# STM32F103ZET6_V2.net
KiCad netlist of a schematic drawn in Altium Designer
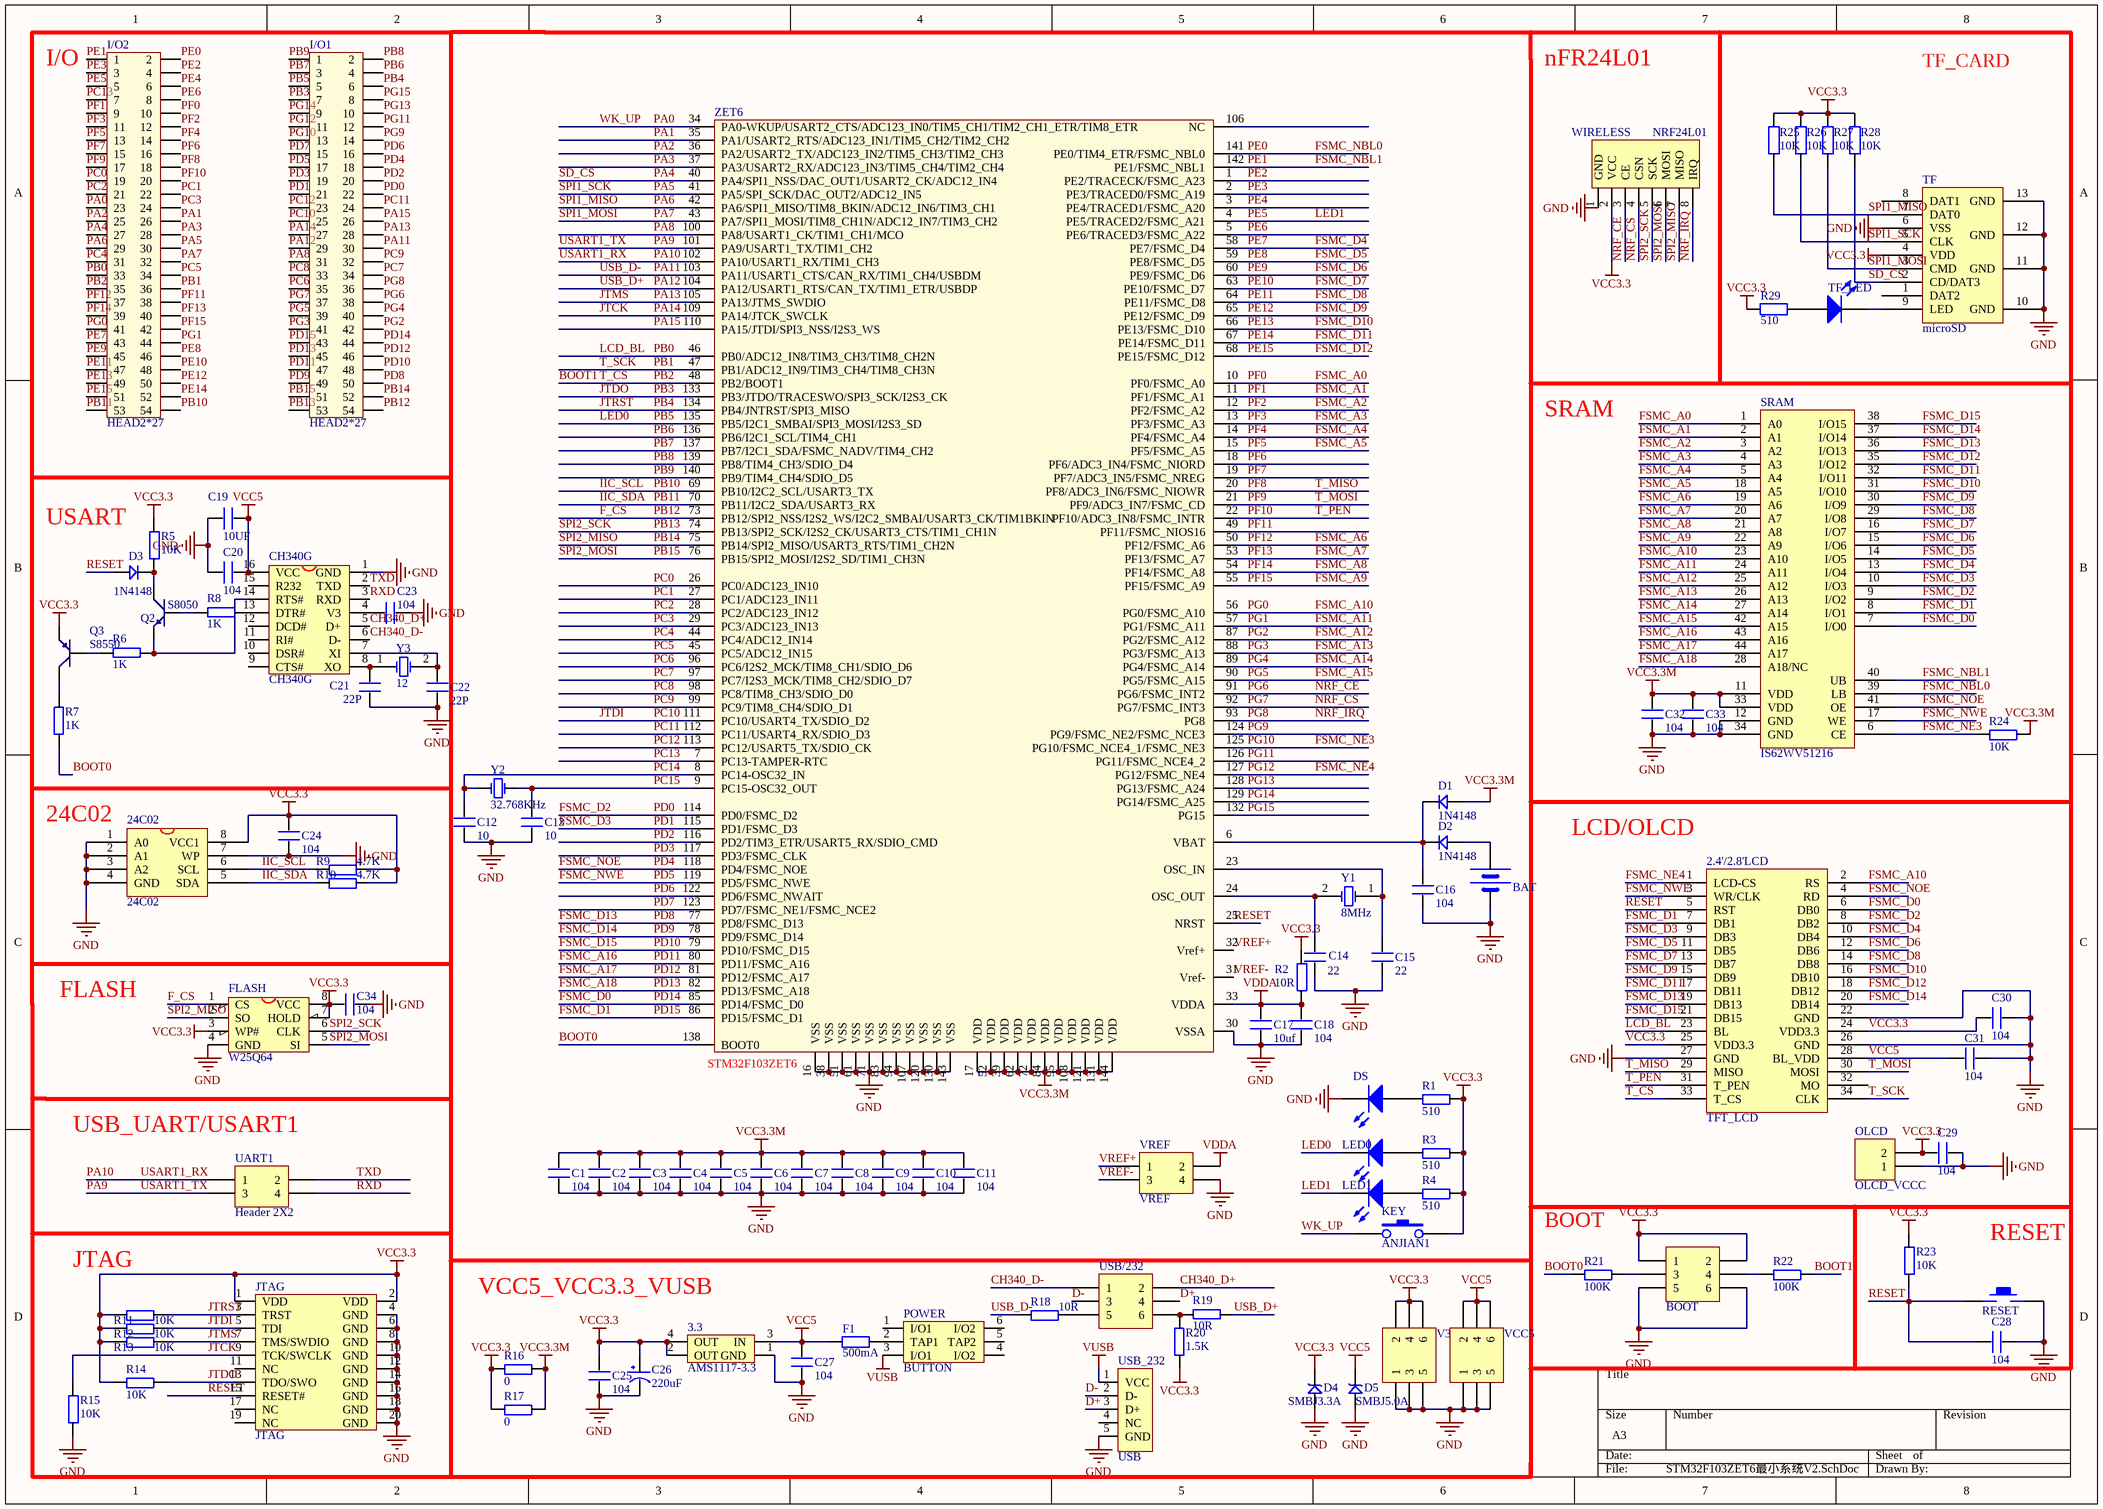
[diagram p0: STM32F103ZET6最小系统V2.SchDoc]

(export (version "E")
  (design (tool "Eeschema 10.0.6"))
  (components
    (comp (ref "2.4'/2.8'LCD")
      (value "TFT_LCD")
      (footprint "DB2*17")
      (libsource (lib "TFT_LCD") (part "TFT_LCD"))
    )
    (comp (ref "3.3")
      (value "AMS1117-3.3")
      (footprint "AMS1117")
      (libsource (lib "战舰STM32开发板底板封装库") (part "AMS1117"))
    )
    (comp (ref "24C02")
      (value "24C02")
      (footprint "SOP-8")
      (libsource (lib "战舰STM32开发板底板封装库") (part "24C256"))
    )
    (comp (ref "BAT") (value "BATT") (footprint "BATM") (libsource (lib "战舰STM32开发板底板封装库") (part "BAT")))
    (comp (ref "BOOT")
      (value "Header 3X2")
      (footprint "HDR2X3")
      (description "Header, 3-Pin, Dual row")
      (fields (field (name "PUBLISHER") "Altium Limited"))
      (libsource (lib "战舰STM32开发板底板封装库") (part "Header 3X2"))
    )
    (comp (ref "C1") (value "104") (footprint "0603P") (libsource (lib "战舰STM32开发板底板封装库") (part "C")))
    (comp (ref "C2") (value "104") (footprint "0603P") (libsource (lib "战舰STM32开发板底板封装库") (part "C")))
    (comp (ref "C3") (value "104") (footprint "0603P") (libsource (lib "战舰STM32开发板底板封装库") (part "C")))
    (comp (ref "C4") (value "104") (footprint "0603P") (libsource (lib "战舰STM32开发板底板封装库") (part "C")))
    (comp (ref "C5") (value "104") (footprint "0603P") (libsource (lib "战舰STM32开发板底板封装库") (part "C")))
    (comp (ref "C6") (value "104") (footprint "0603P") (libsource (lib "战舰STM32开发板底板封装库") (part "C")))
    (comp (ref "C7") (value "104") (footprint "0603P") (libsource (lib "战舰STM32开发板底板封装库") (part "C")))
    (comp (ref "C8") (value "104") (footprint "0603P") (libsource (lib "战舰STM32开发板底板封装库") (part "C")))
    (comp (ref "C9") (value "104") (footprint "0603P") (libsource (lib "战舰STM32开发板底板封装库") (part "C")))
    (comp (ref "C10") (value "104") (footprint "0603P") (libsource (lib "战舰STM32开发板底板封装库") (part "C")))
    (comp (ref "C11") (value "104") (footprint "0603P") (libsource (lib "战舰STM32开发板底板封装库") (part "C")))
    (comp (ref "C12") (value "10") (footprint "0603P") (libsource (lib "战舰STM32开发板底板封装库") (part "C_2")))
    (comp (ref "C13") (value "10") (footprint "0603P") (libsource (lib "战舰STM32开发板底板封装库") (part "C_2")))
    (comp (ref "C14") (value "22") (footprint "0805") (libsource (lib "战舰STM32开发板底板封装库") (part "C_1")))
    (comp (ref "C15") (value "22") (footprint "0805") (libsource (lib "战舰STM32开发板底板封装库") (part "C_1")))
    (comp (ref "C16") (value "104") (footprint "0805") (libsource (lib "战舰STM32开发板底板封装库") (part "C_1")))
    (comp (ref "C17") (value "10uf") (footprint "0805") (libsource (lib "战舰STM32开发板底板封装库") (part "C_1")))
    (comp (ref "C18") (value "104") (footprint "0603P") (libsource (lib "战舰STM32开发板底板封装库") (part "C_1")))
    (comp (ref "C19") (value "10UF") (footprint "0805") (libsource (lib "战舰STM32开发板底板封装库") (part "C_1")))
    (comp (ref "C20") (value "104") (footprint "0805") (libsource (lib "战舰STM32开发板底板封装库") (part "C_1")))
    (comp (ref "C21") (value "22P") (footprint "0805") (libsource (lib "战舰STM32开发板底板封装库") (part "C_2")))
    (comp (ref "C22") (value "22P") (footprint "0805") (libsource (lib "战舰STM32开发板底板封装库") (part "C_2")))
    (comp (ref "C23") (value "104") (footprint "0805") (libsource (lib "战舰STM32开发板底板封装库") (part "C_1")))
    (comp (ref "C24") (value "104") (footprint "0805") (libsource (lib "战舰STM32开发板底板封装库") (part "C_1")))
    (comp (ref "C25") (value "104") (footprint "0805") (libsource (lib "战舰STM32开发板底板封装库") (part "C_1")))
    (comp (ref "C26") (value "220uF") (footprint "CC6.56.5") (libsource (lib "战舰STM32开发板底板封装库") (part "CAP")))
    (comp (ref "C27") (value "104") (footprint "0805") (libsource (lib "战舰STM32开发板底板封装库") (part "C")))
    (comp (ref "C28") (value "104") (footprint "0805") (libsource (lib "战舰STM32开发板底板封装库") (part "C")))
    (comp (ref "C29") (value "104") (footprint "0805") (libsource (lib "战舰STM32开发板底板封装库") (part "C_1")))
    (comp (ref "C30") (value "104") (footprint "0805") (libsource (lib "战舰STM32开发板底板封装库") (part "C")))
    (comp (ref "C31") (value "104") (footprint "0805") (libsource (lib "战舰STM32开发板底板封装库") (part "C")))
    (comp (ref "C32") (value "104") (footprint "0805") (libsource (lib "战舰STM32开发板底板封装库") (part "C_1")))
    (comp (ref "C33") (value "104") (footprint "0805") (libsource (lib "战舰STM32开发板底板封装库") (part "C_1")))
    (comp (ref "C34") (value "104") (footprint "0805") (libsource (lib "战舰STM32开发板底板封装库") (part "C_1")))
    (comp (ref "CH340G")
      (value "CH340G")
      (footprint "SOP16M")
      (description "USB2UART")
      (libsource (lib "战舰STM32开发板底板封装库") (part "CH340G"))
    )
    (comp (ref "D1") (value "1N4148") (footprint "DIODE_SOP") (libsource (lib "战舰STM32开发板底板封装库") (part "D")))
    (comp (ref "D2") (value "1N4148") (footprint "DIODE_SOP") (libsource (lib "战舰STM32开发板底板封装库") (part "D")))
    (comp (ref "D3") (value "1N4148") (footprint "DIODE_SOP") (libsource (lib "战舰STM32开发板底板封装库") (part "D")))
    (comp (ref "D4")
      (value "SMBJ5.0A")
      (footprint "SMBJ")
      (description "TVS")
      (libsource (lib "战舰STM32开发板底板封装库") (part "SMBJ"))
    )
    (comp (ref "D5")
      (value "SMBJ3.3A")
      (footprint "SMBJ")
      (description "TVS")
      (libsource (lib "战舰STM32开发板底板封装库") (part "SMBJ"))
    )
    (comp (ref "DS")
      (value "LED1")
      (footprint "0805")
      (description "Typical RED, GREEN, YELLOW, AMBER GaAs LED")
      (fields (field (name "PUBLISHER") "Altium Limited"))
      (libsource (lib "战舰STM32开发板底板封装库") (part "LED2"))
    )
    (comp (ref "F1")
      (value "500mA")
      (footprint "0805")
      (description "Resistor")
      (fields (field (name "Comment") "Res2") (field (name "PUBLISHER") "Altium Limited"))
      (libsource (lib "") (part "Res2_2"))
    )
    (comp (ref "FLASH")
      (value "W25Q64")
      (footprint "SOIC-8")
      (description "W25X16;SST25VF016;MX25L1605")
      (libsource (lib "战舰STM32开发板底板封装库") (part "W25X16"))
    )
    (comp (ref "I/O1")
      (value "HEAD2*27")
      (footprint "HEAD2*27")
      (libsource (lib "战舰STM32开发板底板封装库") (part "HEAD2*27"))
    )
    (comp (ref "I/O2")
      (value "HEAD2*27")
      (footprint "HEAD2*27")
      (libsource (lib "战舰STM32开发板底板封装库") (part "HEAD2*27"))
    )
    (comp (ref "JTAG") (value "JTAG") (footprint "HDR2X10") (libsource (lib "战舰STM32开发板底板封装库") (part "JTAG")))
    (comp (ref "KEY") (value "ANJIAN1") (footprint "贴片微动开关") (libsource (lib "开关") (part "ANJIAN1")))
    (comp (ref "LED0")
      (value "LED1")
      (footprint "0805")
      (description "Typical RED, GREEN, YELLOW, AMBER GaAs LED")
      (fields (field (name "PUBLISHER") "Altium Limited"))
      (libsource (lib "战舰STM32开发板底板封装库") (part "LED2"))
    )
    (comp (ref "LED1")
      (value "LED1")
      (footprint "0805")
      (description "Typical RED, GREEN, YELLOW, AMBER GaAs LED")
      (fields (field (name "PUBLISHER") "Altium Limited"))
      (libsource (lib "战舰STM32开发板底板封装库") (part "LED2"))
    )
    (comp (ref "OLCD")
      (value "OLCD_VCCC")
      (footprint "HDR1X2")
      (description "Header, 2-Pin, Right Angle")
      (fields (field (name "PUBLISHER") "Altium Limited"))
      (libsource (lib "Miscellaneous Connectors") (part "Header 2H"))
    )
    (comp (ref "POWER")
      (value "BUTTON")
      (footprint "BTN8.5*8.5")
      (libsource (lib "战舰STM32开发板底板封装库") (part "BUTTON"))
    )
    (comp (ref "Q2")
      (value "S8050")
      (footprint "SOT-23R")
      (description "8050/BCW846/BCW847")
      (libsource (lib "战舰STM32开发板底板封装库") (part "NPN"))
    )
    (comp (ref "Q3")
      (value "S8550")
      (footprint "SOT-23R")
      (description "8550/BCW68")
      (libsource (lib "战舰STM32开发板底板封装库") (part "PNP"))
    )
    (comp (ref "R1") (value "510") (footprint "0805") (libsource (lib "战舰STM32开发板底板封装库") (part "R")))
    (comp (ref "R2") (value "10R") (footprint "0805") (libsource (lib "战舰STM32开发板底板封装库") (part "R")))
    (comp (ref "R3") (value "510") (footprint "0805") (libsource (lib "战舰STM32开发板底板封装库") (part "R")))
    (comp (ref "R4") (value "510") (footprint "0805") (libsource (lib "战舰STM32开发板底板封装库") (part "R")))
    (comp (ref "R5") (value "10K") (footprint "0805") (libsource (lib "战舰STM32开发板底板封装库") (part "R")))
    (comp (ref "R6") (value "1K") (footprint "0805") (libsource (lib "战舰STM32开发板底板封装库") (part "R")))
    (comp (ref "R7") (value "1K") (footprint "0805") (libsource (lib "战舰STM32开发板底板封装库") (part "R")))
    (comp (ref "R8") (value "1K") (footprint "0805") (libsource (lib "战舰STM32开发板底板封装库") (part "R")))
    (comp (ref "R9") (value "4.7K") (footprint "0805") (libsource (lib "战舰STM32开发板底板封装库") (part "R")))
    (comp (ref "R10") (value "4.7K") (footprint "0805") (libsource (lib "战舰STM32开发板底板封装库") (part "R")))
    (comp (ref "R11") (value "10K") (footprint "0805") (libsource (lib "战舰STM32开发板底板封装库") (part "R_1")))
    (comp (ref "R12") (value "10K") (footprint "0805") (libsource (lib "战舰STM32开发板底板封装库") (part "R_1")))
    (comp (ref "R13") (value "10K") (footprint "0805") (libsource (lib "战舰STM32开发板底板封装库") (part "R_1")))
    (comp (ref "R14") (value "10K") (footprint "0805") (libsource (lib "战舰STM32开发板底板封装库") (part "R_1")))
    (comp (ref "R15") (value "10K") (footprint "0805") (libsource (lib "战舰STM32开发板底板封装库") (part "R_1")))
    (comp (ref "R16") (value "0") (footprint "0805") (libsource (lib "战舰STM32开发板底板封装库") (part "R")))
    (comp (ref "R17") (value "0") (footprint "0805") (libsource (lib "战舰STM32开发板底板封装库") (part "R")))
    (comp (ref "R18") (value "10R") (footprint "0805") (libsource (lib "战舰STM32开发板底板封装库") (part "R_2")))
    (comp (ref "R19") (value "10R") (footprint "0805") (libsource (lib "战舰STM32开发板底板封装库") (part "R_2")))
    (comp (ref "R20") (value "1.5K") (footprint "0805") (libsource (lib "战舰STM32开发板底板封装库") (part "R_2")))
    (comp (ref "R21") (value "100K") (footprint "0805") (libsource (lib "战舰STM32开发板底板封装库") (part "R_1")))
    (comp (ref "R22") (value "100K") (footprint "0805") (libsource (lib "战舰STM32开发板底板封装库") (part "R_1")))
    (comp (ref "R23") (value "10K") (footprint "0805") (libsource (lib "战舰STM32开发板底板封装库") (part "R_1")))
    (comp (ref "R24") (value "10K") (footprint "0805") (libsource (lib "战舰STM32开发板底板封装库") (part "R")))
    (comp (ref "R25")
      (value "10K")
      (footprint "0805")
      (description "Resistor")
      (fields (field (name "Comment") "Res2") (field (name "PUBLISHER") "Altium Limited"))
      (libsource (lib "Miscellaneous Devices") (part "Res2"))
    )
    (comp (ref "R26")
      (value "10K")
      (footprint "0805")
      (description "Resistor")
      (fields (field (name "Comment") "Res2") (field (name "PUBLISHER") "Altium Limited"))
      (libsource (lib "Miscellaneous Devices") (part "Res2"))
    )
    (comp (ref "R27")
      (value "10K")
      (footprint "0805")
      (description "Resistor")
      (fields (field (name "Comment") "Res2") (field (name "PUBLISHER") "Altium Limited"))
      (libsource (lib "Miscellaneous Devices") (part "Res2"))
    )
    (comp (ref "R28")
      (value "10K")
      (footprint "0805")
      (description "Resistor")
      (fields (field (name "Comment") "Res2") (field (name "PUBLISHER") "Altium Limited"))
      (libsource (lib "Miscellaneous Devices") (part "Res2"))
    )
    (comp (ref "R29")
      (value "510")
      (footprint "0805")
      (description "Resistor")
      (fields (field (name "Comment") "Res2") (field (name "PUBLISHER") "Altium Limited"))
      (libsource (lib "") (part "Res2_1"))
    )
    (comp (ref "RESET")
      (value "KEY_M")
      (footprint "贴片微动开关")
      (libsource (lib "战舰STM32开发板底板封装库") (part "KEY_M"))
    )
    (comp (ref "SRAM")
      (value "IS62WV51216")
      (footprint "TSOP44")
      (libsource (lib "STM32F103常用外设") (part "SRAM"))
    )
    (comp (ref "TF") (value "microSD") (footprint "TF_CARD") (libsource (lib "我自己的库") (part "microSD")))
    (comp (ref "TF_LED")
      (value "LED1")
      (footprint "0805")
      (description "Typical RED, GREEN, YELLOW, AMBER GaAs LED")
      (fields (field (name "PUBLISHER") "Altium Limited"))
      (libsource (lib "战舰STM32开发板底板封装库") (part "LED2"))
    )
    (comp (ref "UART1")
      (value "Header 2X2")
      (footprint "HDR2X2")
      (description "Header, 2-Pin, Dual row")
      (fields (field (name "PUBLISHER") "Altium Limited"))
      (libsource (lib "Miscellaneous Connectors") (part "Header 2X2"))
    )
    (comp (ref "USB/232")
      (value "Header 3X2")
      (footprint "HDR2X3")
      (description "Header, 3-Pin, Dual row")
      (fields (field (name "PUBLISHER") "Altium Limited"))
      (libsource (lib "战舰STM32开发板底板封装库") (part "Header 3X2"))
    )
    (comp (ref "USB_232")
      (value "USB")
      (footprint "USB/SM0.8-6H5")
      (libsource (lib "战舰STM32开发板底板封装库") (part "USB5"))
    )
    (comp (ref "V3.3")
      (value "Header 3X2")
      (footprint "HDR2X3")
      (description "Header, 3-Pin, Dual row")
      (fields (field (name "PUBLISHER") "Altium Limited"))
      (libsource (lib "Miscellaneous Connectors") (part "Header 3X2"))
    )
    (comp (ref "VCC5")
      (value "Header 3X2")
      (footprint "HDR2X3")
      (description "Header, 3-Pin, Dual row")
      (fields (field (name "PUBLISHER") "Altium Limited"))
      (libsource (lib "Miscellaneous Connectors") (part "Header 3X2"))
    )
    (comp (ref "VREF")
      (value "VREF")
      (footprint "HDR2X2")
      (description "Header, 2-Pin, Dual row")
      (fields (field (name "PUBLISHER") "Altium Limited"))
      (libsource (lib "战舰STM32开发板底板封装库") (part "Header 2X2"))
    )
    (comp (ref "WIRELESS")
      (value "NRF24L01")
      (footprint "NRF24L01")
      (libsource (lib "战舰STM32开发板底板封装库") (part "NRF24L01"))
    )
    (comp (ref "Y1")
      (value "8MHz")
      (footprint "XTAL_US")
      (description "Crystal Oscillator")
      (fields (field (name "PUBLISHER") "Altium Limited"))
      (libsource (lib "战舰STM32开发板底板封装库") (part "XTAL"))
    )
    (comp (ref "Y2")
      (value "32.768KHz")
      (footprint "XTAL32")
      (description "32.768K")
      (fields (field (name "PUBLISHER") "Altium Limited"))
      (libsource (lib "战舰STM32开发板底板封装库") (part "XTAL_3"))
    )
    (comp (ref "Y3")
      (value "12")
      (footprint "XTAL_US")
      (description "Crystal Oscillator")
      (fields (field (name "PUBLISHER") "Altium Limited"))
      (libsource (lib "战舰STM32开发板底板封装库") (part "XTAL"))
    )
    (comp (ref "ZET6")
      (value "STM32F103ZET6")
      (footprint "LQFP144")
      (libsource (lib "stm32") (part "STM32F103ZET6"))
    )
  )
  (nets
    (net (code "1") (name "/BOOT0") (class "Default")
      (node (ref "R21") (pin "1") (pintype "passive"))
      (node (ref "R7") (pin "2") (pintype "passive"))
      (node (ref "ZET6") (pin "138") (pinfunction "BOOT0_138") (pintype "passive"))
    )
    (net (code "2") (name "/BOOT1") (class "Default")
      (node (ref "2.4'/2.8'LCD") (pin "33") (pinfunction "T_CS_33") (pintype "passive"))
      (node (ref "I/O2") (pin "35") (pinfunction "35_35") (pintype "passive"))
      (node (ref "R22") (pin "2") (pintype "passive"))
      (node (ref "ZET6") (pin "48") (pinfunction "PB2/BOOT1_48") (pintype "passive"))
    )
    (net (code "3") (name "/CH340_D+") (class "Default")
      (node (ref "CH340G") (pin "5") (pinfunction "D+_5") (pintype "passive"))
      (node (ref "USB/232") (pin "2") (pinfunction "2_2") (pintype "passive"))
    )
    (net (code "4") (name "/CH340_D-") (class "Default")
      (node (ref "CH340G") (pin "6") (pinfunction "D-_6") (pintype "passive"))
      (node (ref "USB/232") (pin "1") (pinfunction "1_1") (pintype "passive"))
    )
    (net (code "5") (name "/D+") (class "Default")
      (node (ref "USB/232") (pin "4") (pinfunction "4_4") (pintype "passive"))
      (node (ref "USB_232") (pin "3") (pinfunction "D+_3") (pintype "passive"))
    )
    (net (code "6") (name "/D-") (class "Default")
      (node (ref "USB/232") (pin "3") (pinfunction "3_3") (pintype "passive"))
      (node (ref "USB_232") (pin "2") (pinfunction "D-_2") (pintype "passive"))
    )
    (net (code "7") (name "/FSMC_A0") (class "Default")
      (node (ref "I/O2") (pin "10") (pinfunction "10_10") (pintype "passive"))
      (node (ref "SRAM") (pin "1") (pinfunction "A0_1") (pintype "passive"))
      (node (ref "ZET6") (pin "10") (pinfunction "PF0/FSMC_A0_10") (pintype "passive"))
    )
    (net (code "8") (name "/FSMC_A1") (class "Default")
      (node (ref "I/O2") (pin "9") (pinfunction "9_9") (pintype "passive"))
      (node (ref "SRAM") (pin "2") (pinfunction "A1_2") (pintype "passive"))
      (node (ref "ZET6") (pin "11") (pinfunction "PF1/FSMC_A1_11") (pintype "passive"))
    )
    (net (code "9") (name "/FSMC_A2") (class "Default")
      (node (ref "I/O2") (pin "12") (pinfunction "12_12") (pintype "passive"))
      (node (ref "SRAM") (pin "3") (pinfunction "A2_3") (pintype "passive"))
      (node (ref "ZET6") (pin "12") (pinfunction "PF2/FSMC_A2_12") (pintype "passive"))
    )
    (net (code "10") (name "/FSMC_A3") (class "Default")
      (node (ref "I/O2") (pin "11") (pinfunction "11_11") (pintype "passive"))
      (node (ref "SRAM") (pin "4") (pinfunction "A3_4") (pintype "passive"))
      (node (ref "ZET6") (pin "13") (pinfunction "PF3/FSMC_A3_13") (pintype "passive"))
    )
    (net (code "11") (name "/FSMC_A4") (class "Default")
      (node (ref "I/O2") (pin "14") (pinfunction "14_14") (pintype "passive"))
      (node (ref "SRAM") (pin "5") (pinfunction "A4_5") (pintype "passive"))
      (node (ref "ZET6") (pin "14") (pinfunction "PF4/FSMC_A4_14") (pintype "passive"))
    )
    (net (code "12") (name "/FSMC_A5") (class "Default")
      (node (ref "I/O2") (pin "13") (pinfunction "13_13") (pintype "passive"))
      (node (ref "SRAM") (pin "18") (pinfunction "A5_18") (pintype "passive"))
      (node (ref "ZET6") (pin "15") (pinfunction "PF5/FSMC_A5_15") (pintype "passive"))
    )
    (net (code "13") (name "/FSMC_A6") (class "Default")
      (node (ref "I/O2") (pin "37") (pinfunction "37_37") (pintype "passive"))
      (node (ref "SRAM") (pin "19") (pinfunction "A6_19") (pintype "passive"))
      (node (ref "ZET6") (pin "50") (pinfunction "PF12/FSMC_A6_50") (pintype "passive"))
    )
    (net (code "14") (name "/FSMC_A7") (class "Default")
      (node (ref "I/O2") (pin "40") (pinfunction "40_40") (pintype "passive"))
      (node (ref "SRAM") (pin "20") (pinfunction "A7_20") (pintype "passive"))
      (node (ref "ZET6") (pin "53") (pinfunction "PF13/FSMC_A7_53") (pintype "passive"))
    )
    (net (code "15") (name "/FSMC_A8") (class "Default")
      (node (ref "I/O2") (pin "39") (pinfunction "39_39") (pintype "passive"))
      (node (ref "SRAM") (pin "21") (pinfunction "A8_21") (pintype "passive"))
      (node (ref "ZET6") (pin "54") (pinfunction "PF14/FSMC_A8_54") (pintype "passive"))
    )
    (net (code "16") (name "/FSMC_A9") (class "Default")
      (node (ref "I/O2") (pin "42") (pinfunction "42_42") (pintype "passive"))
      (node (ref "SRAM") (pin "22") (pinfunction "A9_22") (pintype "passive"))
      (node (ref "ZET6") (pin "55") (pinfunction "PF15/FSMC_A9_55") (pintype "passive"))
    )
    (net (code "17") (name "/FSMC_A10") (class "Default")
      (node (ref "2.4'/2.8'LCD") (pin "2") (pinfunction "RS_2") (pintype "passive"))
      (node (ref "I/O2") (pin "41") (pinfunction "41_41") (pintype "passive"))
      (node (ref "SRAM") (pin "23") (pinfunction "A10_23") (pintype "passive"))
      (node (ref "ZET6") (pin "56") (pinfunction "PG0/FSMC_A10_56") (pintype "passive"))
    )
    (net (code "18") (name "/FSMC_A11") (class "Default")
      (node (ref "I/O2") (pin "44") (pinfunction "44_44") (pintype "passive"))
      (node (ref "SRAM") (pin "24") (pinfunction "A11_24") (pintype "passive"))
      (node (ref "ZET6") (pin "57") (pinfunction "PG1/FSMC_A11_57") (pintype "passive"))
    )
    (net (code "19") (name "/FSMC_A12") (class "Default")
      (node (ref "I/O1") (pin "42") (pinfunction "42_42") (pintype "passive"))
      (node (ref "SRAM") (pin "25") (pinfunction "A12_25") (pintype "passive"))
      (node (ref "ZET6") (pin "87") (pinfunction "PG2/FSMC_A12_87") (pintype "passive"))
    )
    (net (code "20") (name "/FSMC_A13") (class "Default")
      (node (ref "I/O1") (pin "41") (pinfunction "41_41") (pintype "passive"))
      (node (ref "SRAM") (pin "26") (pinfunction "A13_26") (pintype "passive"))
      (node (ref "ZET6") (pin "88") (pinfunction "PG3/FSMC_A13_88") (pintype "passive"))
    )
    (net (code "21") (name "/FSMC_A14") (class "Default")
      (node (ref "I/O1") (pin "40") (pinfunction "40_40") (pintype "passive"))
      (node (ref "SRAM") (pin "27") (pinfunction "A14_27") (pintype "passive"))
      (node (ref "ZET6") (pin "89") (pinfunction "PG4/FSMC_A14_89") (pintype "passive"))
    )
    (net (code "22") (name "/FSMC_A15") (class "Default")
      (node (ref "I/O1") (pin "39") (pinfunction "39_39") (pintype "passive"))
      (node (ref "SRAM") (pin "42") (pinfunction "A15_42") (pintype "passive"))
      (node (ref "ZET6") (pin "90") (pinfunction "PG5/FSMC_A15_90") (pintype "passive"))
    )
    (net (code "23") (name "/FSMC_A16") (class "Default")
      (node (ref "I/O1") (pin "47") (pinfunction "47_47") (pintype "passive"))
      (node (ref "SRAM") (pin "43") (pinfunction "A16_43") (pintype "passive"))
      (node (ref "ZET6") (pin "80") (pinfunction "PD11/FSMC_A16_80") (pintype "passive"))
    )
    (net (code "24") (name "/FSMC_A17") (class "Default")
      (node (ref "I/O1") (pin "46") (pinfunction "46_46") (pintype "passive"))
      (node (ref "SRAM") (pin "44") (pinfunction "A17_44") (pintype "passive"))
      (node (ref "ZET6") (pin "81") (pinfunction "PD12/FSMC_A17_81") (pintype "passive"))
    )
    (net (code "25") (name "/FSMC_A18") (class "Default")
      (node (ref "I/O1") (pin "45") (pinfunction "45_45") (pintype "passive"))
      (node (ref "SRAM") (pin "28") (pinfunction "A18/NC_28") (pintype "passive"))
      (node (ref "ZET6") (pin "82") (pinfunction "PD13/FSMC_A18_82") (pintype "passive"))
    )
    (net (code "26") (name "/FSMC_D0") (class "Default")
      (node (ref "2.4'/2.8'LCD") (pin "6") (pinfunction "DB0_6") (pintype "passive"))
      (node (ref "I/O1") (pin "44") (pinfunction "44_44") (pintype "passive"))
      (node (ref "SRAM") (pin "7") (pinfunction "I/O0_7") (pintype "passive"))
      (node (ref "ZET6") (pin "85") (pinfunction "PD14/FSMC_D0_85") (pintype "passive"))
    )
    (net (code "27") (name "/FSMC_D1") (class "Default")
      (node (ref "2.4'/2.8'LCD") (pin "7") (pinfunction "DB1_7") (pintype "passive"))
      (node (ref "I/O1") (pin "43") (pinfunction "43_43") (pintype "passive"))
      (node (ref "SRAM") (pin "8") (pinfunction "I/O1_8") (pintype "passive"))
      (node (ref "ZET6") (pin "86") (pinfunction "PD15/FSMC_D1_86") (pintype "passive"))
    )
    (net (code "28") (name "/FSMC_D2") (class "Default")
      (node (ref "2.4'/2.8'LCD") (pin "8") (pinfunction "DB2_8") (pintype "passive"))
      (node (ref "I/O1") (pin "22") (pinfunction "22_22") (pintype "passive"))
      (node (ref "SRAM") (pin "9") (pinfunction "I/O2_9") (pintype "passive"))
      (node (ref "ZET6") (pin "114") (pinfunction "PD0/FSMC_D2_114") (pintype "passive"))
    )
    (net (code "29") (name "/FSMC_D3") (class "Default")
      (node (ref "2.4'/2.8'LCD") (pin "9") (pinfunction "DB3_9") (pintype "passive"))
      (node (ref "I/O1") (pin "21") (pinfunction "21_21") (pintype "passive"))
      (node (ref "SRAM") (pin "10") (pinfunction "I/O3_10") (pintype "passive"))
      (node (ref "ZET6") (pin "115") (pinfunction "PD1/FSMC_D3_115") (pintype "passive"))
    )
    (net (code "30") (name "/FSMC_D4") (class "Default")
      (node (ref "2.4'/2.8'LCD") (pin "10") (pinfunction "DB4_10") (pintype "passive"))
      (node (ref "I/O2") (pin "43") (pinfunction "43_43") (pintype "passive"))
      (node (ref "SRAM") (pin "13") (pinfunction "I/O4_13") (pintype "passive"))
      (node (ref "ZET6") (pin "58") (pinfunction "PE7/FSMC_D4_58") (pintype "passive"))
    )
    (net (code "31") (name "/FSMC_D5") (class "Default")
      (node (ref "2.4'/2.8'LCD") (pin "11") (pinfunction "DB5_11") (pintype "passive"))
      (node (ref "I/O2") (pin "46") (pinfunction "46_46") (pintype "passive"))
      (node (ref "SRAM") (pin "14") (pinfunction "I/O5_14") (pintype "passive"))
      (node (ref "ZET6") (pin "59") (pinfunction "PE8/FSMC_D5_59") (pintype "passive"))
    )
    (net (code "32") (name "/FSMC_D6") (class "Default")
      (node (ref "2.4'/2.8'LCD") (pin "12") (pinfunction "DB6_12") (pintype "passive"))
      (node (ref "I/O2") (pin "45") (pinfunction "45_45") (pintype "passive"))
      (node (ref "SRAM") (pin "15") (pinfunction "I/O6_15") (pintype "passive"))
      (node (ref "ZET6") (pin "60") (pinfunction "PE9/FSMC_D6_60") (pintype "passive"))
    )
    (net (code "33") (name "/FSMC_D7") (class "Default")
      (node (ref "2.4'/2.8'LCD") (pin "13") (pinfunction "DB7_13") (pintype "passive"))
      (node (ref "I/O2") (pin "48") (pinfunction "48_48") (pintype "passive"))
      (node (ref "SRAM") (pin "16") (pinfunction "I/O7_16") (pintype "passive"))
      (node (ref "ZET6") (pin "63") (pinfunction "PE10/FSMC_D7_63") (pintype "passive"))
    )
    (net (code "34") (name "/FSMC_D8") (class "Default")
      (node (ref "2.4'/2.8'LCD") (pin "14") (pinfunction "DB8_14") (pintype "passive"))
      (node (ref "I/O2") (pin "47") (pinfunction "47_47") (pintype "passive"))
      (node (ref "SRAM") (pin "29") (pinfunction "I/O8_29") (pintype "passive"))
      (node (ref "ZET6") (pin "64") (pinfunction "PE11/FSMC_D8_64") (pintype "passive"))
    )
    (net (code "35") (name "/FSMC_D9") (class "Default")
      (node (ref "2.4'/2.8'LCD") (pin "15") (pinfunction "DB9_15") (pintype "passive"))
      (node (ref "I/O2") (pin "50") (pinfunction "50_50") (pintype "passive"))
      (node (ref "SRAM") (pin "30") (pinfunction "I/O9_30") (pintype "passive"))
      (node (ref "ZET6") (pin "65") (pinfunction "PE12/FSMC_D9_65") (pintype "passive"))
    )
    (net (code "36") (name "/FSMC_D10") (class "Default")
      (node (ref "2.4'/2.8'LCD") (pin "16") (pinfunction "DB10_16") (pintype "passive"))
      (node (ref "I/O2") (pin "49") (pinfunction "49_49") (pintype "passive"))
      (node (ref "SRAM") (pin "31") (pinfunction "I/O10_31") (pintype "passive"))
      (node (ref "ZET6") (pin "66") (pinfunction "PE13/FSMC_D10_66") (pintype "passive"))
    )
    (net (code "37") (name "/FSMC_D11") (class "Default")
      (node (ref "2.4'/2.8'LCD") (pin "17") (pinfunction "DB11_17") (pintype "passive"))
      (node (ref "I/O2") (pin "52") (pinfunction "52_52") (pintype "passive"))
      (node (ref "SRAM") (pin "32") (pinfunction "I/O11_32") (pintype "passive"))
      (node (ref "ZET6") (pin "67") (pinfunction "PE14/FSMC_D11_67") (pintype "passive"))
    )
    (net (code "38") (name "/FSMC_D12") (class "Default")
      (node (ref "2.4'/2.8'LCD") (pin "18") (pinfunction "DB12_18") (pintype "passive"))
      (node (ref "I/O2") (pin "51") (pinfunction "51_51") (pintype "passive"))
      (node (ref "SRAM") (pin "35") (pinfunction "I/O12_35") (pintype "passive"))
      (node (ref "ZET6") (pin "68") (pinfunction "PE15/FSMC_D12_68") (pintype "passive"))
    )
    (net (code "39") (name "/FSMC_D13") (class "Default")
      (node (ref "2.4'/2.8'LCD") (pin "19") (pinfunction "DB13_19") (pintype "passive"))
      (node (ref "I/O1") (pin "50") (pinfunction "50_50") (pintype "passive"))
      (node (ref "SRAM") (pin "36") (pinfunction "I/O13_36") (pintype "passive"))
      (node (ref "ZET6") (pin "77") (pinfunction "PD8/FSMC_D13_77") (pintype "passive"))
    )
    (net (code "40") (name "/FSMC_D14") (class "Default")
      (node (ref "2.4'/2.8'LCD") (pin "20") (pinfunction "DB14_20") (pintype "passive"))
      (node (ref "I/O1") (pin "49") (pinfunction "49_49") (pintype "passive"))
      (node (ref "SRAM") (pin "37") (pinfunction "I/O14_37") (pintype "passive"))
      (node (ref "ZET6") (pin "78") (pinfunction "PD9/FSMC_D14_78") (pintype "passive"))
    )
    (net (code "41") (name "/FSMC_D15") (class "Default")
      (node (ref "2.4'/2.8'LCD") (pin "21") (pinfunction "DB15_21") (pintype "passive"))
      (node (ref "I/O1") (pin "48") (pinfunction "48_48") (pintype "passive"))
      (node (ref "SRAM") (pin "38") (pinfunction "I/O15_38") (pintype "passive"))
      (node (ref "ZET6") (pin "79") (pinfunction "PD10/FSMC_D15_79") (pintype "passive"))
    )
    (net (code "42") (name "/FSMC_NBL0") (class "Default")
      (node (ref "I/O2") (pin "2") (pinfunction "2_2") (pintype "passive"))
      (node (ref "SRAM") (pin "39") (pinfunction "LB_39") (pintype "passive"))
      (node (ref "ZET6") (pin "141") (pinfunction "PE0/TIM4_ETR/FSMC_NBL0_141") (pintype "passive"))
    )
    (net (code "43") (name "/FSMC_NBL1") (class "Default")
      (node (ref "I/O2") (pin "1") (pinfunction "1_1") (pintype "passive"))
      (node (ref "SRAM") (pin "40") (pinfunction "UB_40") (pintype "passive"))
      (node (ref "ZET6") (pin "142") (pinfunction "PE1/FSMC_NBL1_142") (pintype "passive"))
    )
    (net (code "44") (name "/FSMC_NE3") (class "Default")
      (node (ref "I/O1") (pin "13") (pinfunction "13_13") (pintype "passive"))
      (node (ref "R24") (pin "1") (pintype "passive"))
      (node (ref "SRAM") (pin "6") (pinfunction "CE_6") (pintype "passive"))
      (node (ref "ZET6") (pin "125") (pinfunction "PG10/FSMC_NCE4_1/FSMC_NE3_125") (pintype "passive"))
    )
    (net (code "45") (name "/FSMC_NE4") (class "Default")
      (node (ref "2.4'/2.8'LCD") (pin "1") (pinfunction "LCD-CS_1") (pintype "passive"))
      (node (ref "I/O1") (pin "11") (pinfunction "11_11") (pintype "passive"))
      (node (ref "ZET6") (pin "127") (pinfunction "PG12/FSMC_NE4_127") (pintype "passive"))
    )
    (net (code "46") (name "/FSMC_NOE") (class "Default")
      (node (ref "2.4'/2.8'LCD") (pin "4") (pinfunction "RD_4") (pintype "passive"))
      (node (ref "I/O1") (pin "18") (pinfunction "18_18") (pintype "passive"))
      (node (ref "SRAM") (pin "41") (pinfunction "OE_41") (pintype "passive"))
      (node (ref "ZET6") (pin "118") (pinfunction "PD4/FSMC_NOE_118") (pintype "passive"))
    )
    (net (code "47") (name "/FSMC_NWE") (class "Default")
      (node (ref "2.4'/2.8'LCD") (pin "3") (pinfunction "WR/CLK_3") (pintype "passive"))
      (node (ref "I/O1") (pin "17") (pinfunction "17_17") (pintype "passive"))
      (node (ref "SRAM") (pin "17") (pinfunction "WE_17") (pintype "passive"))
      (node (ref "ZET6") (pin "119") (pinfunction "PD5/FSMC_NWE_119") (pintype "passive"))
    )
    (net (code "48") (name "/F_CS") (class "Default")
      (node (ref "FLASH") (pin "1") (pinfunction "CS_1") (pintype "passive"))
      (node (ref "I/O1") (pin "54") (pinfunction "54_54") (pintype "passive"))
      (node (ref "ZET6") (pin "73") (pinfunction "PB12/SPI2_NSS/I2S2_WS/I2C2_SMBAI/USART3_CK/TIM1BKIN_73") (pintype "passive"))
    )
    (net (code "49") (name "/IIC_SCL") (class "Default")
      (node (ref "24C02") (pin "6") (pinfunction "SCL_6") (pintype "passive"))
      (node (ref "I/O2") (pin "54") (pinfunction "54_54") (pintype "passive"))
      (node (ref "R9") (pin "1") (pintype "passive"))
      (node (ref "ZET6") (pin "69") (pinfunction "PB10/I2C2_SCL/USART3_TX_69") (pintype "passive"))
    )
    (net (code "50") (name "/IIC_SDA") (class "Default")
      (node (ref "24C02") (pin "5") (pinfunction "SDA_5") (pintype "passive"))
      (node (ref "I/O2") (pin "53") (pinfunction "53_53") (pintype "passive"))
      (node (ref "R10") (pin "1") (pintype "passive"))
      (node (ref "ZET6") (pin "70") (pinfunction "PB11/I2C2_SDA/USART3_RX_70") (pintype "passive"))
    )
    (net (code "51") (name "/JTCK") (class "Default")
      (node (ref "I/O1") (pin "27") (pinfunction "27_27") (pintype "passive"))
      (node (ref "JTAG") (pin "9") (pinfunction "TCK/SWCLK_9") (pintype "passive"))
      (node (ref "R15") (pin "2") (pintype "passive"))
      (node (ref "ZET6") (pin "109") (pinfunction "PA14/JTCK_SWCLK_109") (pintype "passive"))
    )
    (net (code "52") (name "/JTDI") (class "Default")
      (node (ref "I/O1") (pin "25") (pinfunction "25_25") (pintype "passive"))
      (node (ref "JTAG") (pin "5") (pinfunction "TDI_5") (pintype "passive"))
      (node (ref "R12") (pin "2") (pintype "passive"))
      (node (ref "ZET6") (pin "111") (pinfunction "PC10/USART4_TX/SDIO_D2_111") (pintype "passive"))
    )
    (net (code "53") (name "/JTDO") (class "Default")
      (node (ref "I/O1") (pin "7") (pinfunction "7_7") (pintype "passive"))
      (node (ref "JTAG") (pin "13") (pinfunction "TDO/SWO_13") (pintype "passive"))
      (node (ref "R14") (pin "2") (pintype "passive"))
      (node (ref "ZET6") (pin "133") (pinfunction "PB3/JTDO/TRACESWO/SPI3_SCK/I2S3_CK_133") (pintype "passive"))
    )
    (net (code "54") (name "/JTMS") (class "Default")
      (node (ref "I/O1") (pin "28") (pinfunction "28_28") (pintype "passive"))
      (node (ref "JTAG") (pin "7") (pinfunction "TMS/SWDIO_7") (pintype "passive"))
      (node (ref "R13") (pin "2") (pintype "passive"))
      (node (ref "ZET6") (pin "105") (pinfunction "PA13/JTMS_SWDIO_105") (pintype "passive"))
    )
    (net (code "55") (name "/JTRST") (class "Default")
      (node (ref "I/O1") (pin "6") (pinfunction "6_6") (pintype "passive"))
      (node (ref "JTAG") (pin "3") (pinfunction "TRST_3") (pintype "passive"))
      (node (ref "R11") (pin "2") (pintype "passive"))
      (node (ref "ZET6") (pin "134") (pinfunction "PB4/JNTRST/SPI3_MISO_134") (pintype "passive"))
    )
    (net (code "56") (name "/LCD_BL") (class "Default")
      (node (ref "2.4'/2.8'LCD") (pin "23") (pinfunction "BL_23") (pintype "passive"))
      (node (ref "I/O2") (pin "33") (pinfunction "33_33") (pintype "passive"))
      (node (ref "ZET6") (pin "46") (pinfunction "PB0/ADC12_IN8/TIM3_CH3/TIM8_CH2N_46") (pintype "passive"))
    )
    (net (code "57") (name "/LED0") (class "Default")
      (node (ref "I/O1") (pin "5") (pinfunction "5_5") (pintype "passive"))
      (node (ref "LED0") (pin "2") (pinfunction "K_2") (pintype "passive"))
      (node (ref "ZET6") (pin "135") (pinfunction "PB5/I2C1_SMBAI/SPI3_MOSI/I2S3_SD_135") (pintype "passive"))
    )
    (net (code "58") (name "/LED1") (class "Default")
      (node (ref "I/O2") (pin "5") (pinfunction "5_5") (pintype "passive"))
      (node (ref "LED1") (pin "2") (pinfunction "K_2") (pintype "passive"))
      (node (ref "ZET6") (pin "4") (pinfunction "PE5/TRACED2/FSMC_A21_4") (pintype "passive"))
    )
    (net (code "59") (name "/NRF_CE") (class "Default")
      (node (ref "I/O1") (pin "38") (pinfunction "38_38") (pintype "passive"))
      (node (ref "WIRELESS") (pin "3") (pinfunction "CE_3") (pintype "passive"))
      (node (ref "ZET6") (pin "91") (pinfunction "PG6/FSMC_INT2_91") (pintype "passive"))
    )
    (net (code "60") (name "/NRF_CS") (class "Default")
      (node (ref "I/O1") (pin "37") (pinfunction "37_37") (pintype "passive"))
      (node (ref "WIRELESS") (pin "4") (pinfunction "CSN_4") (pintype "passive"))
      (node (ref "ZET6") (pin "92") (pinfunction "PG7/FSMC_INT3_92") (pintype "passive"))
    )
    (net (code "61") (name "/NRF_IRQ") (class "Default")
      (node (ref "I/O1") (pin "36") (pinfunction "36_36") (pintype "passive"))
      (node (ref "WIRELESS") (pin "8") (pinfunction "IRQ_8") (pintype "passive"))
      (node (ref "ZET6") (pin "93") (pinfunction "PG8_93") (pintype "passive"))
    )
    (net (code "62") (name "/PA0") (class "Default")
      (node (ref "I/O2") (pin "23") (pinfunction "23_23") (pintype "passive"))
      (node (ref "KEY") (pin "1") (pinfunction "1_1") (pintype "passive"))
      (node (ref "ZET6") (pin "34") (pinfunction "PA0-WKUP/USART2_CTS/ADC123_IN0/TIM5_CH1/TIM2_CH1_ETR/TIM8_ETR_34") (pintype "passive"))
    )
    (net (code "63") (name "/PA1") (class "Default")
      (node (ref "I/O2") (pin "26") (pinfunction "26_26") (pintype "passive"))
      (node (ref "ZET6") (pin "35") (pinfunction "PA1/USART2_RTS/ADC123_IN1/TIM5_CH2/TIM2_CH2_35") (pintype "passive"))
    )
    (net (code "64") (name "/PA2") (class "Default")
      (node (ref "I/O2") (pin "25") (pinfunction "25_25") (pintype "passive"))
      (node (ref "ZET6") (pin "36") (pinfunction "PA2/USART2_TX/ADC123_IN2/TIM5_CH3/TIM2_CH3_36") (pintype "passive"))
    )
    (net (code "65") (name "/PA3") (class "Default")
      (node (ref "I/O2") (pin "28") (pinfunction "28_28") (pintype "passive"))
      (node (ref "ZET6") (pin "37") (pinfunction "PA3/USART2_RX/ADC123_IN3/TIM5_CH4/TIM2_CH4_37") (pintype "passive"))
    )
    (net (code "66") (name "/PA4") (class "Default")
      (node (ref "I/O2") (pin "27") (pinfunction "27_27") (pintype "passive"))
      (node (ref "R28") (pin "1") (pinfunction "1_1") (pintype "passive"))
      (node (ref "TF") (pin "2") (pinfunction "CD/DAT3_2") (pintype "passive"))
      (node (ref "ZET6") (pin "40") (pinfunction "PA4/SPI1_NSS/DAC_OUT1/USART2_CK/ADC12_IN4_40") (pintype "passive"))
    )
    (net (code "67") (name "/PA5") (class "Default")
      (node (ref "I/O2") (pin "30") (pinfunction "30_30") (pintype "passive"))
      (node (ref "R26") (pin "1") (pinfunction "1_1") (pintype "passive"))
      (node (ref "TF") (pin "5") (pinfunction "CLK_5") (pintype "passive"))
      (node (ref "ZET6") (pin "41") (pinfunction "PA5/SPI_SCK/DAC_OUT2/ADC12_IN5_41") (pintype "passive"))
    )
    (net (code "68") (name "/PA6") (class "Default")
      (node (ref "I/O2") (pin "29") (pinfunction "29_29") (pintype "passive"))
      (node (ref "R25") (pin "1") (pinfunction "1_1") (pintype "passive"))
      (node (ref "TF") (pin "7") (pinfunction "DAT0_7") (pintype "passive"))
      (node (ref "ZET6") (pin "42") (pinfunction "PA6/SPI1_MISO/TIM8_BKIN/ADC12_IN6/TIM3_CH1_42") (pintype "passive"))
    )
    (net (code "69") (name "/PA7") (class "Default")
      (node (ref "I/O2") (pin "32") (pinfunction "32_32") (pintype "passive"))
      (node (ref "R27") (pin "1") (pinfunction "1_1") (pintype "passive"))
      (node (ref "TF") (pin "3") (pinfunction "CMD_3") (pintype "passive"))
      (node (ref "ZET6") (pin "43") (pinfunction "PA7/SPI1_MOSI/TIM8_CH1N/ADC12_IN7/TIM3_CH2_43") (pintype "passive"))
    )
    (net (code "70") (name "/PA8") (class "Default")
      (node (ref "I/O1") (pin "31") (pinfunction "31_31") (pintype "passive"))
      (node (ref "ZET6") (pin "100") (pinfunction "PA8/USART1_CK/TIM1_CH1/MCO_100") (pintype "passive"))
    )
    (net (code "71") (name "/PA9") (class "Default")
      (node (ref "UART1") (pin "3") (pinfunction "3_3") (pintype "passive"))
      (node (ref "ZET6") (pin "101") (pinfunction "PA9/USART1_TX/TIM1_CH2_101") (pintype "passive"))
    )
    (net (code "72") (name "/PA10") (class "Default")
      (node (ref "UART1") (pin "1") (pinfunction "1_1") (pintype "passive"))
      (node (ref "ZET6") (pin "102") (pinfunction "PA10/USART1_RX/TIM1_CH3_102") (pintype "passive"))
    )
    (net (code "73") (name "/PA11") (class "Default")
      (node (ref "I/O1") (pin "30") (pinfunction "30_30") (pintype "passive"))
      (node (ref "R18") (pin "1") (pintype "passive"))
      (node (ref "ZET6") (pin "103") (pinfunction "PA11/USART1_CTS/CAN_RX/TIM1_CH4/USBDM_103") (pintype "passive"))
    )
    (net (code "74") (name "/PA12") (class "Default")
      (node (ref "I/O1") (pin "29") (pinfunction "29_29") (pintype "passive"))
      (node (ref "R19") (pin "1") (pintype "passive"))
      (node (ref "ZET6") (pin "104") (pinfunction "PA12/USART1_RTS/CAN_TX/TIM1_ETR/USBDP_104") (pintype "passive"))
    )
    (net (code "75") (name "/PA15") (class "Default")
      (node (ref "I/O1") (pin "26") (pinfunction "26_26") (pintype "passive"))
      (node (ref "ZET6") (pin "110") (pinfunction "PA15/JTDI/SPI3_NSS/I2S3_WS_110") (pintype "passive"))
    )
    (net (code "76") (name "/PB1") (class "Default")
      (node (ref "2.4'/2.8'LCD") (pin "34") (pinfunction "CLK_34") (pintype "passive"))
      (node (ref "I/O2") (pin "36") (pinfunction "36_36") (pintype "passive"))
      (node (ref "ZET6") (pin "47") (pinfunction "PB1/ADC12_IN9/TIM3_CH4/TIM8_CH3N_47") (pintype "passive"))
    )
    (net (code "77") (name "/PB6") (class "Default")
      (node (ref "I/O1") (pin "4") (pinfunction "4_4") (pintype "passive"))
      (node (ref "ZET6") (pin "136") (pinfunction "PB6/I2C1_SCL/TIM4_CH1_136") (pintype "passive"))
    )
    (net (code "78") (name "/PB7") (class "Default")
      (node (ref "I/O1") (pin "3") (pinfunction "3_3") (pintype "passive"))
      (node (ref "ZET6") (pin "137") (pinfunction "PB7/I2C1_SDA/FSMC_NADV/TIM4_CH2_137") (pintype "passive"))
    )
    (net (code "79") (name "/PB8") (class "Default")
      (node (ref "I/O1") (pin "2") (pinfunction "2_2") (pintype "passive"))
      (node (ref "ZET6") (pin "139") (pinfunction "PB8/TIM4_CH3/SDIO_D4_139") (pintype "passive"))
    )
    (net (code "80") (name "/PB9") (class "Default")
      (node (ref "I/O1") (pin "1") (pinfunction "1_1") (pintype "passive"))
      (node (ref "ZET6") (pin "140") (pinfunction "PB9/TIM4_CH4/SDIO_D5_140") (pintype "passive"))
    )
    (net (code "81") (name "/PB13") (class "Default")
      (node (ref "FLASH") (pin "6") (pinfunction "CLK_6") (pintype "passive"))
      (node (ref "I/O1") (pin "53") (pinfunction "53_53") (pintype "passive"))
      (node (ref "WIRELESS") (pin "5") (pinfunction "SCK_5") (pintype "passive"))
      (node (ref "ZET6") (pin "74") (pinfunction "PB13/SPI2_SCK/I2S2_CK/USART3_CTS/TIM1_CH1N_74") (pintype "passive"))
    )
    (net (code "82") (name "/PB14") (class "Default")
      (node (ref "FLASH") (pin "2") (pinfunction "SO_2") (pintype "passive"))
      (node (ref "I/O1") (pin "52") (pinfunction "52_52") (pintype "passive"))
      (node (ref "WIRELESS") (pin "7") (pinfunction "MISO_7") (pintype "passive"))
      (node (ref "ZET6") (pin "75") (pinfunction "PB14/SPI2_MISO/USART3_RTS/TIM1_CH2N_75") (pintype "passive"))
    )
    (net (code "83") (name "/PB15") (class "Default")
      (node (ref "FLASH") (pin "5") (pinfunction "SI_5") (pintype "passive"))
      (node (ref "I/O1") (pin "51") (pinfunction "51_51") (pintype "passive"))
      (node (ref "WIRELESS") (pin "6") (pinfunction "MOSI_6") (pintype "passive"))
      (node (ref "ZET6") (pin "76") (pinfunction "PB15/SPI2_MOSI/I2S2_SD/TIM1_CH3N_76") (pintype "passive"))
    )
    (net (code "84") (name "/PC0") (class "Default")
      (node (ref "I/O2") (pin "19") (pinfunction "19_19") (pintype "passive"))
      (node (ref "ZET6") (pin "26") (pinfunction "PC0/ADC123_IN10_26") (pintype "passive"))
    )
    (net (code "85") (name "/PC1") (class "Default")
      (node (ref "I/O2") (pin "22") (pinfunction "22_22") (pintype "passive"))
      (node (ref "ZET6") (pin "27") (pinfunction "PC1/ADC123_IN11_27") (pintype "passive"))
    )
    (net (code "86") (name "/PC2") (class "Default")
      (node (ref "I/O2") (pin "21") (pinfunction "21_21") (pintype "passive"))
      (node (ref "ZET6") (pin "28") (pinfunction "PC2/ADC123_IN12_28") (pintype "passive"))
    )
    (net (code "87") (name "/PC3") (class "Default")
      (node (ref "I/O2") (pin "24") (pinfunction "24_24") (pintype "passive"))
      (node (ref "ZET6") (pin "29") (pinfunction "PC3/ADC123_IN13_29") (pintype "passive"))
    )
    (net (code "88") (name "/PC4") (class "Default")
      (node (ref "I/O2") (pin "31") (pinfunction "31_31") (pintype "passive"))
      (node (ref "ZET6") (pin "44") (pinfunction "PC4/ADC12_IN14_44") (pintype "passive"))
    )
    (net (code "89") (name "/PC5") (class "Default")
      (node (ref "I/O2") (pin "34") (pinfunction "34_34") (pintype "passive"))
      (node (ref "ZET6") (pin "45") (pinfunction "PC5/ADC12_IN15_45") (pintype "passive"))
    )
    (net (code "90") (name "/PC6") (class "Default")
      (node (ref "I/O1") (pin "35") (pinfunction "35_35") (pintype "passive"))
      (node (ref "ZET6") (pin "96") (pinfunction "PC6/I2S2_MCK/TIM8_CH1/SDIO_D6_96") (pintype "passive"))
    )
    (net (code "91") (name "/PC7") (class "Default")
      (node (ref "I/O1") (pin "34") (pinfunction "34_34") (pintype "passive"))
      (node (ref "ZET6") (pin "97") (pinfunction "PC7/I2S3_MCK/TIM8_CH2/SDIO_D7_97") (pintype "passive"))
    )
    (net (code "92") (name "/PC8") (class "Default")
      (node (ref "I/O1") (pin "33") (pinfunction "33_33") (pintype "passive"))
      (node (ref "ZET6") (pin "98") (pinfunction "PC8/TIM8_CH3/SDIO_D0_98") (pintype "passive"))
    )
    (net (code "93") (name "/PC9") (class "Default")
      (node (ref "I/O1") (pin "32") (pinfunction "32_32") (pintype "passive"))
      (node (ref "ZET6") (pin "99") (pinfunction "PC9/TIM8_CH4/SDIO_D1_99") (pintype "passive"))
    )
    (net (code "94") (name "/PC11") (class "Default")
      (node (ref "I/O1") (pin "24") (pinfunction "24_24") (pintype "passive"))
      (node (ref "ZET6") (pin "112") (pinfunction "PC11/USART4_RX/SDIO_D3_112") (pintype "passive"))
    )
    (net (code "95") (name "/PC12") (class "Default")
      (node (ref "I/O1") (pin "23") (pinfunction "23_23") (pintype "passive"))
      (node (ref "ZET6") (pin "113") (pinfunction "PC12/USART5_TX/SDIO_CK_113") (pintype "passive"))
    )
    (net (code "96") (name "/PC13") (class "Default")
      (node (ref "I/O2") (pin "7") (pinfunction "7_7") (pintype "passive"))
      (node (ref "ZET6") (pin "7") (pinfunction "PC13-TAMPER-RTC_7") (pintype "passive"))
    )
    (net (code "97") (name "/PC14") (class "Default")
      (node (ref "C12") (pin "2") (pintype "passive"))
      (node (ref "Y2") (pin "2") (pinfunction "OSC2_2") (pintype "passive"))
      (node (ref "ZET6") (pin "8") (pinfunction "PC14-OSC32_IN_8") (pintype "passive"))
    )
    (net (code "98") (name "/PC15") (class "Default")
      (node (ref "C13") (pin "2") (pintype "passive"))
      (node (ref "Y2") (pin "1") (pinfunction "OSC1_1") (pintype "passive"))
      (node (ref "ZET6") (pin "9") (pinfunction "PC15-OSC32_OUT_9") (pintype "passive"))
    )
    (net (code "99") (name "/PD2") (class "Default")
      (node (ref "I/O1") (pin "20") (pinfunction "20_20") (pintype "passive"))
      (node (ref "ZET6") (pin "116") (pinfunction "PD2/TIM3_ETR/USART5_RX/SDIO_CMD_116") (pintype "passive"))
    )
    (net (code "100") (name "/PD3") (class "Default")
      (node (ref "I/O1") (pin "19") (pinfunction "19_19") (pintype "passive"))
      (node (ref "ZET6") (pin "117") (pinfunction "PD3/FSMC_CLK_117") (pintype "passive"))
    )
    (net (code "101") (name "/PD6") (class "Default")
      (node (ref "I/O1") (pin "16") (pinfunction "16_16") (pintype "passive"))
      (node (ref "ZET6") (pin "122") (pinfunction "PD6/FSMC_NWAIT_122") (pintype "passive"))
    )
    (net (code "102") (name "/PD7") (class "Default")
      (node (ref "I/O1") (pin "15") (pinfunction "15_15") (pintype "passive"))
      (node (ref "ZET6") (pin "123") (pinfunction "PD7/FSMC_NE1/FSMC_NCE2_123") (pintype "passive"))
    )
    (net (code "103") (name "/PE2") (class "Default")
      (node (ref "I/O2") (pin "4") (pinfunction "4_4") (pintype "passive"))
      (node (ref "ZET6") (pin "1") (pinfunction "PE2/TRACECK/FSMC_A23_1") (pintype "passive"))
    )
    (net (code "104") (name "/PE3") (class "Default")
      (node (ref "I/O2") (pin "3") (pinfunction "3_3") (pintype "passive"))
      (node (ref "ZET6") (pin "2") (pinfunction "PE3/TRACED0/FSMC_A19_2") (pintype "passive"))
    )
    (net (code "105") (name "/PE4") (class "Default")
      (node (ref "I/O2") (pin "6") (pinfunction "6_6") (pintype "passive"))
      (node (ref "ZET6") (pin "3") (pinfunction "PE4/TRACED1/FSMC_A20_3") (pintype "passive"))
    )
    (net (code "106") (name "/PE6") (class "Default")
      (node (ref "I/O2") (pin "8") (pinfunction "8_8") (pintype "passive"))
      (node (ref "ZET6") (pin "5") (pinfunction "PE6/TRACED3/FSMC_A22_5") (pintype "passive"))
    )
    (net (code "107") (name "/PF6") (class "Default")
      (node (ref "I/O2") (pin "16") (pinfunction "16_16") (pintype "passive"))
      (node (ref "ZET6") (pin "18") (pinfunction "PF6/ADC3_IN4/FSMC_NIORD_18") (pintype "passive"))
    )
    (net (code "108") (name "/PF7") (class "Default")
      (node (ref "I/O2") (pin "15") (pinfunction "15_15") (pintype "passive"))
      (node (ref "ZET6") (pin "19") (pinfunction "PF7/ADC3_IN5/FSMC_NREG_19") (pintype "passive"))
    )
    (net (code "109") (name "/PF8") (class "Default")
      (node (ref "2.4'/2.8'LCD") (pin "29") (pinfunction "MISO_29") (pintype "passive"))
      (node (ref "I/O2") (pin "18") (pinfunction "18_18") (pintype "passive"))
      (node (ref "ZET6") (pin "20") (pinfunction "PF8/ADC3_IN6/FSMC_NIOWR_20") (pintype "passive"))
    )
    (net (code "110") (name "/PF9") (class "Default")
      (node (ref "2.4'/2.8'LCD") (pin "30") (pinfunction "MOSI_30") (pintype "passive"))
      (node (ref "I/O2") (pin "17") (pinfunction "17_17") (pintype "passive"))
      (node (ref "ZET6") (pin "21") (pinfunction "PF9/ADC3_IN7/FSMC_CD_21") (pintype "passive"))
    )
    (net (code "111") (name "/PF10") (class "Default")
      (node (ref "2.4'/2.8'LCD") (pin "31") (pinfunction "T_PEN_31") (pintype "passive"))
      (node (ref "I/O2") (pin "20") (pinfunction "20_20") (pintype "passive"))
      (node (ref "ZET6") (pin "22") (pinfunction "PF10/ADC3_IN8/FSMC_INTR_22") (pintype "passive"))
    )
    (net (code "112") (name "/PF11") (class "Default")
      (node (ref "I/O2") (pin "38") (pinfunction "38_38") (pintype "passive"))
      (node (ref "ZET6") (pin "49") (pinfunction "PF11/FSMC_NIOS16_49") (pintype "passive"))
    )
    (net (code "113") (name "/PG9") (class "Default")
      (node (ref "I/O1") (pin "14") (pinfunction "14_14") (pintype "passive"))
      (node (ref "ZET6") (pin "124") (pinfunction "PG9/FSMC_NE2/FSMC_NCE3_124") (pintype "passive"))
    )
    (net (code "114") (name "/PG11") (class "Default")
      (node (ref "I/O1") (pin "12") (pinfunction "12_12") (pintype "passive"))
      (node (ref "ZET6") (pin "126") (pinfunction "PG11/FSMC_NCE4_2_126") (pintype "passive"))
    )
    (net (code "115") (name "/PG13") (class "Default")
      (node (ref "I/O1") (pin "10") (pinfunction "10_10") (pintype "passive"))
      (node (ref "ZET6") (pin "128") (pinfunction "PG13/FSMC_A24_128") (pintype "passive"))
    )
    (net (code "116") (name "/PG14") (class "Default")
      (node (ref "I/O1") (pin "9") (pinfunction "9_9") (pintype "passive"))
      (node (ref "ZET6") (pin "129") (pinfunction "PG14/FSMC_A25_129") (pintype "passive"))
    )
    (net (code "117") (name "/PG15") (class "Default")
      (node (ref "I/O1") (pin "8") (pinfunction "8_8") (pintype "passive"))
      (node (ref "ZET6") (pin "132") (pinfunction "PG15_132") (pintype "passive"))
    )
    (net (code "118") (name "/RESET") (class "Default")
      (node (ref "2.4'/2.8'LCD") (pin "5") (pinfunction "RST_5") (pintype "passive"))
      (node (ref "C28") (pin "1") (pintype "passive"))
      (node (ref "D3") (pin "1") (pintype "passive"))
      (node (ref "JTAG") (pin "15") (pinfunction "RESET#_15") (pintype "passive"))
      (node (ref "R23") (pin "1") (pintype "passive"))
      (node (ref "RESET") (pin "1") (pinfunction "1_1") (pintype "passive"))
      (node (ref "ZET6") (pin "25") (pinfunction "NRST_25") (pintype "passive"))
    )
    (net (code "119") (name "/RXD") (class "Default")
      (node (ref "CH340G") (pin "3") (pinfunction "RXD_3") (pintype "passive"))
      (node (ref "UART1") (pin "4") (pinfunction "4_4") (pintype "passive"))
    )
    (net (code "120") (name "/TXD") (class "Default")
      (node (ref "CH340G") (pin "2") (pinfunction "TXD_2") (pintype "passive"))
      (node (ref "UART1") (pin "2") (pinfunction "2_2") (pintype "passive"))
    )
    (net (code "121") (name "/VREF+") (class "Default")
      (node (ref "VREF") (pin "1") (pinfunction "1_1") (pintype "passive"))
      (node (ref "ZET6") (pin "32") (pinfunction "Vref+_32") (pintype "passive"))
    )
    (net (code "122") (name "/VREF-") (class "Default")
      (node (ref "VREF") (pin "3") (pinfunction "3_3") (pintype "passive"))
      (node (ref "ZET6") (pin "31") (pinfunction "Vref-_31") (pintype "passive"))
    )
    (net (code "123") (name "GND") (class "Default")
      (node (ref "2.4'/2.8'LCD") (pin "22") (pinfunction "GND_22") (pintype "passive"))
      (node (ref "2.4'/2.8'LCD") (pin "26") (pinfunction "GND_26") (pintype "passive"))
      (node (ref "2.4'/2.8'LCD") (pin "27") (pinfunction "GND_27") (pintype "passive"))
      (node (ref "24C02") (pin "1") (pinfunction "A0_1") (pintype "passive"))
      (node (ref "24C02") (pin "2") (pinfunction "A1_2") (pintype "passive"))
      (node (ref "24C02") (pin "3") (pinfunction "A2_3") (pintype "passive"))
      (node (ref "24C02") (pin "4") (pinfunction "GND_4") (pintype "passive"))
      (node (ref "24C02") (pin "7") (pinfunction "WP_7") (pintype "passive"))
      (node (ref "3.3") (pin "1") (pinfunction "GND_1") (pintype "passive"))
      (node (ref "BAT") (pin "2") (pinfunction "GND_2") (pintype "passive"))
      (node (ref "BOOT") (pin "5") (pinfunction "5_5") (pintype "passive"))
      (node (ref "BOOT") (pin "6") (pinfunction "6_6") (pintype "passive"))
      (node (ref "C1") (pin "1") (pintype "passive"))
      (node (ref "C10") (pin "1") (pintype "passive"))
      (node (ref "C11") (pin "1") (pintype "passive"))
      (node (ref "C12") (pin "1") (pintype "passive"))
      (node (ref "C13") (pin "1") (pintype "passive"))
      (node (ref "C14") (pin "1") (pintype "passive"))
      (node (ref "C15") (pin "1") (pintype "passive"))
      (node (ref "C16") (pin "1") (pintype "passive"))
      (node (ref "C17") (pin "1") (pintype "passive"))
      (node (ref "C18") (pin "1") (pintype "passive"))
      (node (ref "C19") (pin "1") (pintype "passive"))
      (node (ref "C2") (pin "1") (pintype "passive"))
      (node (ref "C20") (pin "1") (pintype "passive"))
      (node (ref "C21") (pin "1") (pintype "passive"))
      (node (ref "C22") (pin "1") (pintype "passive"))
      (node (ref "C23") (pin "2") (pintype "passive"))
      (node (ref "C24") (pin "1") (pintype "passive"))
      (node (ref "C25") (pin "1") (pintype "passive"))
      (node (ref "C26") (pin "2") (pinfunction "GND_2") (pintype "passive"))
      (node (ref "C27") (pin "1") (pintype "passive"))
      (node (ref "C28") (pin "2") (pintype "passive"))
      (node (ref "C29") (pin "1") (pintype "passive"))
      (node (ref "C3") (pin "1") (pintype "passive"))
      (node (ref "C30") (pin "2") (pintype "passive"))
      (node (ref "C31") (pin "2") (pintype "passive"))
      (node (ref "C32") (pin "1") (pintype "passive"))
      (node (ref "C33") (pin "1") (pintype "passive"))
      (node (ref "C34") (pin "1") (pintype "passive"))
      (node (ref "C4") (pin "1") (pintype "passive"))
      (node (ref "C5") (pin "1") (pintype "passive"))
      (node (ref "C6") (pin "1") (pintype "passive"))
      (node (ref "C7") (pin "1") (pintype "passive"))
      (node (ref "C8") (pin "1") (pintype "passive"))
      (node (ref "C9") (pin "1") (pintype "passive"))
      (node (ref "CH340G") (pin "1") (pinfunction "GND_1") (pintype "passive"))
      (node (ref "D4") (pin "1") (pintype "passive"))
      (node (ref "D5") (pin "1") (pintype "passive"))
      (node (ref "DS") (pin "2") (pinfunction "K_2") (pintype "passive"))
      (node (ref "FLASH") (pin "4") (pinfunction "GND_4") (pintype "passive"))
      (node (ref "JTAG") (pin "10") (pinfunction "GND_10") (pintype "passive"))
      (node (ref "JTAG") (pin "12") (pinfunction "GND_12") (pintype "passive"))
      (node (ref "JTAG") (pin "14") (pinfunction "GND_14") (pintype "passive"))
      (node (ref "JTAG") (pin "16") (pinfunction "GND_16") (pintype "passive"))
      (node (ref "JTAG") (pin "18") (pinfunction "GND_18") (pintype "passive"))
      (node (ref "JTAG") (pin "20") (pinfunction "GND_20") (pintype "passive"))
      (node (ref "JTAG") (pin "4") (pinfunction "GND_4") (pintype "passive"))
      (node (ref "JTAG") (pin "6") (pinfunction "GND_6") (pintype "passive"))
      (node (ref "JTAG") (pin "8") (pinfunction "GND_8") (pintype "passive"))
      (node (ref "OLCD") (pin "1") (pinfunction "1_1") (pintype "passive"))
      (node (ref "R15") (pin "1") (pintype "passive"))
      (node (ref "RESET") (pin "2") (pinfunction "2_2") (pintype "passive"))
      (node (ref "SRAM") (pin "12") (pinfunction "GND_12") (pintype "passive"))
      (node (ref "SRAM") (pin "34") (pinfunction "GND_34") (pintype "passive"))
      (node (ref "TF") (pin "10") (pinfunction "GND_10") (pintype "passive"))
      (node (ref "TF") (pin "11") (pinfunction "GND_11") (pintype "passive"))
      (node (ref "TF") (pin "12") (pinfunction "GND_12") (pintype "passive"))
      (node (ref "TF") (pin "13") (pinfunction "GND_13") (pintype "passive"))
      (node (ref "TF") (pin "6") (pinfunction "VSS_6") (pintype "passive"))
      (node (ref "USB_232") (pin "5") (pinfunction "GND_5") (pintype "passive"))
      (node (ref "V3.3") (pin "1") (pinfunction "1_1") (pintype "passive"))
      (node (ref "V3.3") (pin "3") (pinfunction "3_3") (pintype "passive"))
      (node (ref "V3.3") (pin "5") (pinfunction "5_5") (pintype "passive"))
      (node (ref "VCC5") (pin "1") (pinfunction "1_1") (pintype "passive"))
      (node (ref "VCC5") (pin "3") (pinfunction "3_3") (pintype "passive"))
      (node (ref "VCC5") (pin "5") (pinfunction "5_5") (pintype "passive"))
      (node (ref "VREF") (pin "4") (pinfunction "4_4") (pintype "passive"))
      (node (ref "WIRELESS") (pin "1") (pinfunction "GND_1") (pintype "passive"))
      (node (ref "ZET6") (pin "107") (pinfunction "VSS_107") (pintype "passive"))
      (node (ref "ZET6") (pin "120") (pinfunction "VSS_120") (pintype "passive"))
      (node (ref "ZET6") (pin "130") (pinfunction "VSS_130") (pintype "passive"))
      (node (ref "ZET6") (pin "143") (pinfunction "VSS_143") (pintype "passive"))
      (node (ref "ZET6") (pin "16") (pinfunction "VSS_16") (pintype "passive"))
      (node (ref "ZET6") (pin "30") (pinfunction "VSSA_30") (pintype "passive"))
      (node (ref "ZET6") (pin "38") (pinfunction "VSS_38") (pintype "passive"))
      (node (ref "ZET6") (pin "51") (pinfunction "VSS_51") (pintype "passive"))
      (node (ref "ZET6") (pin "61") (pinfunction "VSS_61") (pintype "passive"))
      (node (ref "ZET6") (pin "71") (pinfunction "VSS_71") (pintype "passive"))
      (node (ref "ZET6") (pin "83") (pinfunction "VSS_83") (pintype "passive"))
      (node (ref "ZET6") (pin "94") (pinfunction "VSS_94") (pintype "passive"))
    )
    (net (code "124") (name "Net-(BAT-VCC)") (class "Default")
      (node (ref "BAT") (pin "1") (pinfunction "VCC_1") (pintype "passive"))
      (node (ref "D2") (pin "1") (pintype "passive"))
    )
    (net (code "125") (name "Net-(BOOT-Pad3)") (class "Default")
      (node (ref "BOOT") (pin "3") (pinfunction "3_3") (pintype "passive"))
      (node (ref "R21") (pin "2") (pintype "passive"))
    )
    (net (code "126") (name "Net-(BOOT-Pad4)") (class "Default")
      (node (ref "BOOT") (pin "4") (pinfunction "4_4") (pintype "passive"))
      (node (ref "R22") (pin "1") (pintype "passive"))
    )
    (net (code "127") (name "Net-(CH340G-DTR#)") (class "Default")
      (node (ref "CH340G") (pin "13") (pinfunction "DTR#_13") (pintype "passive"))
      (node (ref "R8") (pin "1") (pintype "passive"))
    )
    (net (code "128") (name "Net-(CH340G-RTS#)") (class "Default")
      (node (ref "CH340G") (pin "14") (pinfunction "RTS#_14") (pintype "passive"))
      (node (ref "Q2") (pin "1") (pinfunction "E_1") (pintype "passive"))
      (node (ref "R6") (pin "1") (pintype "passive"))
    )
    (net (code "129") (name "Net-(CH340G-V3)") (class "Default")
      (node (ref "C23") (pin "1") (pintype "passive"))
      (node (ref "CH340G") (pin "4") (pinfunction "V3_4") (pintype "passive"))
    )
    (net (code "130") (name "Net-(CH340G-XI)") (class "Default")
      (node (ref "C22") (pin "2") (pintype "passive"))
      (node (ref "CH340G") (pin "7") (pinfunction "XI_7") (pintype "passive"))
      (node (ref "Y3") (pin "2") (pinfunction "OSC2_2") (pintype "passive"))
    )
    (net (code "131") (name "Net-(CH340G-XO)") (class "Default")
      (node (ref "C21") (pin "2") (pintype "passive"))
      (node (ref "CH340G") (pin "8") (pinfunction "XO_8") (pintype "passive"))
      (node (ref "Y3") (pin "1") (pinfunction "OSC1_1") (pintype "passive"))
    )
    (net (code "132") (name "Net-(DS-A)") (class "Default")
      (node (ref "DS") (pin "1") (pinfunction "A_1") (pintype "passive"))
      (node (ref "R1") (pin "1") (pintype "passive"))
    )
    (net (code "133") (name "Net-(LED0-A)") (class "Default")
      (node (ref "LED0") (pin "1") (pinfunction "A_1") (pintype "passive"))
      (node (ref "R3") (pin "1") (pintype "passive"))
    )
    (net (code "134") (name "Net-(LED1-A)") (class "Default")
      (node (ref "LED1") (pin "1") (pinfunction "A_1") (pintype "passive"))
      (node (ref "R4") (pin "1") (pintype "passive"))
    )
    (net (code "135") (name "Net-(POWER-TAP1)") (class "Default")
      (node (ref "F1") (pin "2") (pinfunction "2_2") (pintype "passive"))
      (node (ref "POWER") (pin "2") (pinfunction "TAP1_2") (pintype "passive"))
    )
    (net (code "136") (name "Net-(Q2-B)") (class "Default")
      (node (ref "Q2") (pin "2") (pinfunction "B_2") (pintype "passive"))
      (node (ref "R8") (pin "2") (pintype "passive"))
    )
    (net (code "137") (name "Net-(Q2-C)") (class "Default")
      (node (ref "D3") (pin "2") (pintype "passive"))
      (node (ref "Q2") (pin "3") (pinfunction "C_3") (pintype "passive"))
      (node (ref "R5") (pin "1") (pintype "passive"))
    )
    (net (code "138") (name "Net-(Q3-B)") (class "Default")
      (node (ref "Q3") (pin "2") (pinfunction "B_2") (pintype "passive"))
      (node (ref "R6") (pin "2") (pintype "passive"))
    )
    (net (code "139") (name "Net-(Q3-C)") (class "Default")
      (node (ref "Q3") (pin "3") (pinfunction "C_3") (pintype "passive"))
      (node (ref "R7") (pin "1") (pintype "passive"))
    )
    (net (code "140") (name "Net-(R18-Pad2)") (class "Default")
      (node (ref "R18") (pin "2") (pintype "passive"))
      (node (ref "USB/232") (pin "5") (pinfunction "5_5") (pintype "passive"))
    )
    (net (code "141") (name "Net-(R19-Pad2)") (class "Default")
      (node (ref "R19") (pin "2") (pintype "passive"))
      (node (ref "R20") (pin "1") (pintype "passive"))
      (node (ref "USB/232") (pin "6") (pinfunction "6_6") (pintype "passive"))
    )
    (net (code "142") (name "Net-(TF-LED)") (class "Default")
      (node (ref "TF") (pin "9") (pinfunction "LED_9") (pintype "passive"))
      (node (ref "TF_LED") (pin "2") (pinfunction "K_2") (pintype "passive"))
    )
    (net (code "143") (name "Net-(TF_LED-A)") (class "Default")
      (node (ref "R29") (pin "1") (pinfunction "1_1") (pintype "passive"))
      (node (ref "TF_LED") (pin "1") (pinfunction "A_1") (pintype "passive"))
    )
    (net (code "144") (name "Net-(Y1-OSC1)") (class "Default")
      (node (ref "C15") (pin "2") (pintype "passive"))
      (node (ref "Y1") (pin "1") (pinfunction "OSC1_1") (pintype "passive"))
      (node (ref "ZET6") (pin "23") (pinfunction "OSC_IN_23") (pintype "passive"))
    )
    (net (code "145") (name "Net-(Y1-OSC2)") (class "Default")
      (node (ref "C14") (pin "2") (pintype "passive"))
      (node (ref "Y1") (pin "2") (pinfunction "OSC2_2") (pintype "passive"))
      (node (ref "ZET6") (pin "24") (pinfunction "OSC_OUT_24") (pintype "passive"))
    )
    (net (code "146") (name "Net-(ZET6-VBAT)") (class "Default")
      (node (ref "C16") (pin "2") (pintype "passive"))
      (node (ref "D1") (pin "2") (pintype "passive"))
      (node (ref "D2") (pin "2") (pintype "passive"))
      (node (ref "ZET6") (pin "6") (pinfunction "VBAT_6") (pintype "passive"))
    )
    (net (code "147") (name "VCC3.3") (class "Default")
      (node (ref "2.4'/2.8'LCD") (pin "24") (pinfunction "VDD3.3_24") (pintype "passive"))
      (node (ref "2.4'/2.8'LCD") (pin "25") (pinfunction "VDD3.3_25") (pintype "passive"))
      (node (ref "24C02") (pin "8") (pinfunction "VCC1_8") (pintype "passive"))
      (node (ref "3.3") (pin "2") (pinfunction "OUT_2") (pintype "passive"))
      (node (ref "3.3") (pin "4") (pinfunction "OUT_4") (pintype "passive"))
      (node (ref "BOOT") (pin "1") (pinfunction "1_1") (pintype "passive"))
      (node (ref "BOOT") (pin "2") (pinfunction "2_2") (pintype "passive"))
      (node (ref "C24") (pin "2") (pintype "passive"))
      (node (ref "C25") (pin "2") (pintype "passive"))
      (node (ref "C26") (pin "1") (pinfunction "VCC_1") (pintype "passive"))
      (node (ref "C29") (pin "2") (pintype "passive"))
      (node (ref "C30") (pin "1") (pintype "passive"))
      (node (ref "C34") (pin "2") (pintype "passive"))
      (node (ref "D4") (pin "2") (pintype "passive"))
      (node (ref "FLASH") (pin "3") (pinfunction "WP#_3") (pintype "passive"))
      (node (ref "FLASH") (pin "7") (pinfunction "HOLD_7") (pintype "passive"))
      (node (ref "FLASH") (pin "8") (pinfunction "VCC_8") (pintype "passive"))
      (node (ref "JTAG") (pin "1") (pinfunction "VDD_1") (pintype "passive"))
      (node (ref "JTAG") (pin "2") (pinfunction "VDD_2") (pintype "passive"))
      (node (ref "KEY") (pin "2") (pinfunction "2_2") (pintype "passive"))
      (node (ref "OLCD") (pin "2") (pinfunction "2_2") (pintype "passive"))
      (node (ref "Q3") (pin "1") (pinfunction "E_1") (pintype "passive"))
      (node (ref "R1") (pin "2") (pintype "passive"))
      (node (ref "R10") (pin "2") (pintype "passive"))
      (node (ref "R11") (pin "1") (pintype "passive"))
      (node (ref "R12") (pin "1") (pintype "passive"))
      (node (ref "R13") (pin "1") (pintype "passive"))
      (node (ref "R14") (pin "1") (pintype "passive"))
      (node (ref "R16") (pin "1") (pintype "passive"))
      (node (ref "R17") (pin "1") (pintype "passive"))
      (node (ref "R2") (pin "2") (pintype "passive"))
      (node (ref "R20") (pin "2") (pintype "passive"))
      (node (ref "R23") (pin "2") (pintype "passive"))
      (node (ref "R25") (pin "2") (pinfunction "2_2") (pintype "passive"))
      (node (ref "R26") (pin "2") (pinfunction "2_2") (pintype "passive"))
      (node (ref "R27") (pin "2") (pinfunction "2_2") (pintype "passive"))
      (node (ref "R28") (pin "2") (pinfunction "2_2") (pintype "passive"))
      (node (ref "R29") (pin "2") (pinfunction "2_2") (pintype "passive"))
      (node (ref "R3") (pin "2") (pintype "passive"))
      (node (ref "R4") (pin "2") (pintype "passive"))
      (node (ref "R5") (pin "2") (pintype "passive"))
      (node (ref "R9") (pin "2") (pintype "passive"))
      (node (ref "TF") (pin "4") (pinfunction "VDD_4") (pintype "passive"))
      (node (ref "V3.3") (pin "2") (pinfunction "2_2") (pintype "passive"))
      (node (ref "V3.3") (pin "4") (pinfunction "4_4") (pintype "passive"))
      (node (ref "V3.3") (pin "6") (pinfunction "6_6") (pintype "passive"))
      (node (ref "WIRELESS") (pin "2") (pinfunction "VCC_2") (pintype "passive"))
    )
    (net (code "148") (name "VCC3.3M") (class "Default")
      (node (ref "C1") (pin "2") (pintype "passive"))
      (node (ref "C10") (pin "2") (pintype "passive"))
      (node (ref "C11") (pin "2") (pintype "passive"))
      (node (ref "C2") (pin "2") (pintype "passive"))
      (node (ref "C3") (pin "2") (pintype "passive"))
      (node (ref "C32") (pin "2") (pintype "passive"))
      (node (ref "C33") (pin "2") (pintype "passive"))
      (node (ref "C4") (pin "2") (pintype "passive"))
      (node (ref "C5") (pin "2") (pintype "passive"))
      (node (ref "C6") (pin "2") (pintype "passive"))
      (node (ref "C7") (pin "2") (pintype "passive"))
      (node (ref "C8") (pin "2") (pintype "passive"))
      (node (ref "C9") (pin "2") (pintype "passive"))
      (node (ref "D1") (pin "1") (pintype "passive"))
      (node (ref "R16") (pin "2") (pintype "passive"))
      (node (ref "R17") (pin "2") (pintype "passive"))
      (node (ref "R24") (pin "2") (pintype "passive"))
      (node (ref "SRAM") (pin "11") (pinfunction "VDD_11") (pintype "passive"))
      (node (ref "SRAM") (pin "33") (pinfunction "VDD_33") (pintype "passive"))
      (node (ref "ZET6") (pin "108") (pinfunction "VDD_108") (pintype "passive"))
      (node (ref "ZET6") (pin "121") (pinfunction "VDD_121") (pintype "passive"))
      (node (ref "ZET6") (pin "131") (pinfunction "VDD_131") (pintype "passive"))
      (node (ref "ZET6") (pin "144") (pinfunction "VDD_144") (pintype "passive"))
      (node (ref "ZET6") (pin "17") (pinfunction "VDD_17") (pintype "passive"))
      (node (ref "ZET6") (pin "39") (pinfunction "VDD_39") (pintype "passive"))
      (node (ref "ZET6") (pin "52") (pinfunction "VDD_52") (pintype "passive"))
      (node (ref "ZET6") (pin "62") (pinfunction "VDD_62") (pintype "passive"))
      (node (ref "ZET6") (pin "72") (pinfunction "VDD_72") (pintype "passive"))
      (node (ref "ZET6") (pin "84") (pinfunction "VDD_84") (pintype "passive"))
      (node (ref "ZET6") (pin "95") (pinfunction "VDD_95") (pintype "passive"))
    )
    (net (code "149") (name "VCC5") (class "Default")
      (node (ref "2.4'/2.8'LCD") (pin "28") (pinfunction "BL_VDD_28") (pintype "passive"))
      (node (ref "3.3") (pin "3") (pinfunction "IN_3") (pintype "passive"))
      (node (ref "C19") (pin "2") (pintype "passive"))
      (node (ref "C20") (pin "2") (pintype "passive"))
      (node (ref "C27") (pin "2") (pintype "passive"))
      (node (ref "C31") (pin "1") (pintype "passive"))
      (node (ref "CH340G") (pin "16") (pinfunction "VCC_16") (pintype "passive"))
      (node (ref "D5") (pin "2") (pintype "passive"))
      (node (ref "F1") (pin "1") (pinfunction "1_1") (pintype "passive"))
      (node (ref "VCC5") (pin "2") (pinfunction "2_2") (pintype "passive"))
      (node (ref "VCC5") (pin "4") (pinfunction "4_4") (pintype "passive"))
      (node (ref "VCC5") (pin "6") (pinfunction "6_6") (pintype "passive"))
    )
    (net (code "150") (name "VDDA") (class "Default")
      (node (ref "C17") (pin "2") (pintype "passive"))
      (node (ref "C18") (pin "2") (pintype "passive"))
      (node (ref "R2") (pin "1") (pintype "passive"))
      (node (ref "VREF") (pin "2") (pinfunction "2_2") (pintype "passive"))
      (node (ref "ZET6") (pin "33") (pinfunction "VDDA_33") (pintype "passive"))
    )
    (net (code "151") (name "VUSB") (class "Default")
      (node (ref "POWER") (pin "3") (pinfunction "I/O1_3") (pintype "passive"))
      (node (ref "USB_232") (pin "1") (pinfunction "VCC_1") (pintype "passive"))
    )
    (net (code "152") (name "unconnected-(2.4'/2.8'LCD-MO-Pad32)") (class "Default")
      (node (ref "2.4'/2.8'LCD") (pin "32") (pinfunction "MO_32") (pintype "passive"))
    )
    (net (code "153") (name "unconnected-(CH340G-CTS#-Pad9)") (class "Default")
      (node (ref "CH340G") (pin "9") (pinfunction "CTS#_9") (pintype "passive"))
    )
    (net (code "154") (name "unconnected-(CH340G-DCD#-Pad12)") (class "Default")
      (node (ref "CH340G") (pin "12") (pinfunction "DCD#_12") (pintype "passive"))
    )
    (net (code "155") (name "unconnected-(CH340G-DSR#-Pad10)") (class "Default")
      (node (ref "CH340G") (pin "10") (pinfunction "DSR#_10") (pintype "passive"))
    )
    (net (code "156") (name "unconnected-(CH340G-R232-Pad15)") (class "Default")
      (node (ref "CH340G") (pin "15") (pinfunction "R232_15") (pintype "passive"))
    )
    (net (code "157") (name "unconnected-(CH340G-RI#-Pad11)") (class "Default")
      (node (ref "CH340G") (pin "11") (pinfunction "RI#_11") (pintype "passive"))
    )
    (net (code "158") (name "unconnected-(JTAG-NC-Pad11)") (class "Default")
      (node (ref "JTAG") (pin "11") (pinfunction "NC_11") (pintype "passive"))
    )
    (net (code "159") (name "unconnected-(JTAG-NC-Pad17)") (class "Default")
      (node (ref "JTAG") (pin "17") (pinfunction "NC_17") (pintype "passive"))
    )
    (net (code "160") (name "unconnected-(JTAG-NC-Pad19)") (class "Default")
      (node (ref "JTAG") (pin "19") (pinfunction "NC_19") (pintype "passive"))
    )
    (net (code "161") (name "unconnected-(POWER-I{slash}O1-Pad1)") (class "Default")
      (node (ref "POWER") (pin "1") (pinfunction "I/O1_1") (pintype "passive"))
    )
    (net (code "162") (name "unconnected-(POWER-I{slash}O2-Pad4)") (class "Default")
      (node (ref "POWER") (pin "4") (pinfunction "I/O2_4") (pintype "passive"))
    )
    (net (code "163") (name "unconnected-(POWER-I{slash}O2-Pad6)") (class "Default")
      (node (ref "POWER") (pin "6") (pinfunction "I/O2_6") (pintype "passive"))
    )
    (net (code "164") (name "unconnected-(POWER-TAP2-Pad5)") (class "Default")
      (node (ref "POWER") (pin "5") (pinfunction "TAP2_5") (pintype "passive"))
    )
    (net (code "165") (name "unconnected-(TF-DAT1-Pad8)") (class "Default")
      (node (ref "TF") (pin "8") (pinfunction "DAT1_8") (pintype "passive"))
    )
    (net (code "166") (name "unconnected-(TF-DAT2-Pad1)") (class "Default")
      (node (ref "TF") (pin "1") (pinfunction "DAT2_1") (pintype "passive"))
    )
    (net (code "167") (name "unconnected-(USB_232-NC-Pad4)") (class "Default")
      (node (ref "USB_232") (pin "4") (pinfunction "NC_4") (pintype "passive"))
    )
    (net (code "168") (name "unconnected-(ZET6-NC-Pad106)") (class "Default")
      (node (ref "ZET6") (pin "106") (pinfunction "NC_106") (pintype "passive"))
    )
  )
)
